# 5V_and_3V3_Outputs.net
KiCad netlist of a schematic drawn in Altium Designer
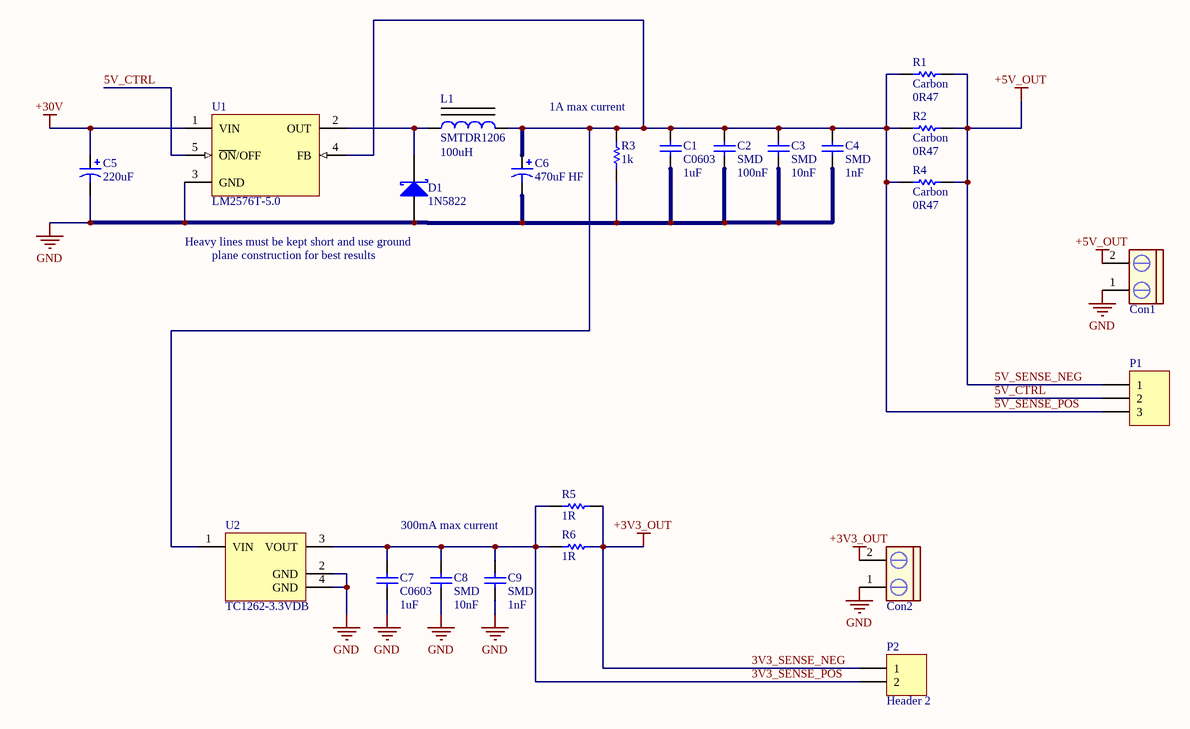
[diagram p0: 5V and 3V3 Outputs.SchDoc]

(export (version "E")
  (design (tool "Eeschema 10.0.6"))
  (components
    (comp (ref "C1")
      (value "C0603")
      (footprint "0603")
      (description "C1608X7R1C105K X7R")
      (fields (field (name "ALTIUM_VALUE") "1uF") (field (name "PUBLISHER") "Altium Limited"))
      (libsource (lib "KEMET Chip Capacitor") (part "C0603"))
    )
    (comp (ref "C2")
      (value "SMD")
      (footprint "1206")
      (description "Ceramic Chip Capacitor - Standard")
      (fields (field (name "ALTIUM_VALUE") "100nF") (field (name "PUBLISHER") "Altium Limited"))
      (libsource (lib "KEMET Chip Capacitor") (part "C1206"))
    )
    (comp (ref "C3")
      (value "SMD")
      (footprint "1206")
      (description "Ceramic Chip Capacitor - Standard")
      (fields (field (name "ALTIUM_VALUE") "10nF") (field (name "PUBLISHER") "Altium Limited"))
      (libsource (lib "KEMET Chip Capacitor") (part "C1206"))
    )
    (comp (ref "C4")
      (value "SMD")
      (footprint "1206")
      (description "Ceramic Chip Capacitor - Standard")
      (fields (field (name "ALTIUM_VALUE") "1nF") (field (name "PUBLISHER") "Altium Limited"))
      (libsource (lib "KEMET Chip Capacitor") (part "C1206"))
    )
    (comp (ref "C5")
      (value "220uF")
      (footprint "CAPPR5-10X16")
      (description "Aluminum Electrolytic Capacitor, Radial Style with Long Leads: 220uF, 63V")
      (fields (field (name "PUBLISHER") "Altium Limited"))
      (libsource (lib "Vishay Roederstein Electrolytic Radial-Lead Capacitor") (part "EKA00DD322J00"))
    )
    (comp (ref "C6")
      (value "470uF HF")
      (footprint "CAPPR5-10X20")
      (description "Aluminum Electrolytic Capacitor, Radial Style with Long Leads: 470uF, 25V")
      (fields (field (name "PUBLISHER") "Altium Limited"))
      (libsource (lib "Vishay Roederstein Electrolytic Radial-Lead Capacitor") (part "EKC00DE347E00"))
    )
    (comp (ref "C7")
      (value "C0603")
      (footprint "0603")
      (description "C1608X7R1C105K X7R")
      (fields (field (name "ALTIUM_VALUE") "1uF") (field (name "PUBLISHER") "Altium Limited"))
      (libsource (lib "KEMET Chip Capacitor") (part "C0603"))
    )
    (comp (ref "C8")
      (value "SMD")
      (footprint "1206")
      (description "Ceramic Chip Capacitor - Standard")
      (fields (field (name "ALTIUM_VALUE") "10nF") (field (name "PUBLISHER") "Altium Limited"))
      (libsource (lib "KEMET Chip Capacitor") (part "C1206"))
    )
    (comp (ref "C9")
      (value "SMD")
      (footprint "1206")
      (description "Ceramic Chip Capacitor - Standard")
      (fields (field (name "ALTIUM_VALUE") "1nF") (field (name "PUBLISHER") "Altium Limited"))
      (libsource (lib "KEMET Chip Capacitor") (part "C1206"))
    )
    (comp (ref "Con1")
      (value "Salida Buck")
      (footprint "My_CN2")
      (description "Connector blue screw")
      (libsource (lib "Mylib") (part "CON2 pin blue"))
    )
    (comp (ref "Con2")
      (value "Salida Buck")
      (footprint "My_CN2")
      (description "Connector blue screw")
      (libsource (lib "Mylib") (part "CON2 pin blue"))
    )
    (comp (ref "D1")
      (value "1N5822")
      (footprint "Vertical DO-201AD")
      (description "Generic Schottky Diode")
      (libsource (lib "NXT - Diodes") (part "Generic Schottky Diode"))
    )
    (comp (ref "L1")
      (value "SMTDR1206")
      (footprint "SMTDR1206 Inductor")
      (description "100UHY SMD 18.54X7.11MM 20% 3A 0.19E SMTDR1206-101M")
      (fields (field (name "ALTIUM_VALUE") "100uH"))
      (libsource (lib "NXT - Inductors") (part "100UHY SMD 18.54X7.11MM 20% 3A 0.19E SMTDR1206-101M"))
    )
    (comp (ref "P1")
      (value "Header 3")
      (footprint "My_1X03")
      (description "Header, 3-Pin")
      (fields (field (name "PUBLISHER") "Altium Limited"))
      (libsource (lib "Mylib") (part "Header 3"))
    )
    (comp (ref "P2")
      (value "Header 2")
      (footprint "HDR1X2")
      (description "Header, 2-Pin")
      (fields (field (name "PUBLISHER") "Altium Limited"))
      (libsource (lib "Miscellaneous Connectors") (part "Header 2"))
    )
    (comp (ref "R1")
      (value "Carbon")
      (footprint "AXIAL-0.3")
      (description "Resistor")
      (fields (field (name "ALTIUM_VALUE") "0R47") (field (name "PUBLISHER") "Altium Limited"))
      (libsource (lib "Miscellaneous Devices") (part "Res1"))
    )
    (comp (ref "R2")
      (value "Carbon")
      (footprint "AXIAL-0.3")
      (description "Resistor")
      (fields (field (name "ALTIUM_VALUE") "0R47") (field (name "PUBLISHER") "Altium Limited"))
      (libsource (lib "Miscellaneous Devices") (part "Res1"))
    )
    (comp (ref "R3")
      (value "1k")
      (footprint "8RB-1206")
      (fields (field (name "Comment") "SMD") (field (name "PUBLISHER") "Altium Limited"))
      (libsource (lib "Panasonic Resistor") (part "ERJ8BQ"))
    )
    (comp (ref "R4")
      (value "Carbon")
      (footprint "AXIAL-0.3")
      (description "Resistor")
      (fields (field (name "ALTIUM_VALUE") "0R47") (field (name "PUBLISHER") "Altium Limited"))
      (libsource (lib "Miscellaneous Devices") (part "Res1"))
    )
    (comp (ref "R5")
      (value "1R")
      (footprint "8RB-1206")
      (fields (field (name "Comment") "SMD") (field (name "PUBLISHER") "Altium Limited"))
      (libsource (lib "Panasonic Resistor") (part "ERJ8BQ"))
    )
    (comp (ref "R6")
      (value "1R")
      (footprint "8RB-1206")
      (fields (field (name "Comment") "SMD") (field (name "PUBLISHER") "Altium Limited"))
      (libsource (lib "Panasonic Resistor") (part "ERJ8BQ"))
    )
    (comp (ref "U1")
      (value "LM2576T-5.0")
      (footprint "T05A")
      (description "SIMPLE SWITCHER® 3A Step-Down Voltage Regulator, 5-pin TO-220")
      (fields
        (field (name "MANUFACTURER") "National Semiconductor")
        (field (name "PUBLISHER") "Altium Limited")
      )
      (libsource (lib "NSC Switcher") (part "LM2576T-5.0"))
    )
    (comp (ref "U2")
      (value "TC1262-3.3VDB")
      (footprint "SOT-223-DB3_N")
      (description "500mA Fixed Output CMOS LDO, 3-Pin SOT-223, Extended Temperature")
      (fields (field (name "PUBLISHER") "Altium Limited"))
      (libsource (lib "Microchip Power Mgt Line Regulator") (part "TC1262-3.3VDB"))
    )
  )
  (nets
    (net (code "1") (name "+3V3_OUT") (class "Default")
      (node (ref "Con2") (pin "2") (pinfunction "2_2") (pintype "passive"))
      (node (ref "P2") (pin "1") (pinfunction "1_1") (pintype "passive"))
      (node (ref "R5") (pin "2") (pinfunction "2_2") (pintype "passive"))
      (node (ref "R6") (pin "2") (pinfunction "2_2") (pintype "passive"))
    )
    (net (code "2") (name "+5V_OUT") (class "Default")
      (node (ref "Con1") (pin "2") (pinfunction "2_2") (pintype "passive"))
      (node (ref "P1") (pin "1") (pinfunction "1_1") (pintype "passive"))
      (node (ref "R1") (pin "2") (pinfunction "2_2") (pintype "passive"))
      (node (ref "R2") (pin "2") (pinfunction "2_2") (pintype "passive"))
      (node (ref "R4") (pin "2") (pinfunction "2_2") (pintype "passive"))
    )
    (net (code "3") (name "+30V") (class "Default")
      (node (ref "C5") (pin "1") (pinfunction "1_1") (pintype "passive"))
      (node (ref "U1") (pin "1") (pinfunction "VIN_1") (pintype "power_in"))
    )
    (net (code "4") (name "/3V3_SENSE_POS") (class "Default")
      (node (ref "C7") (pin "2") (pinfunction "2_2") (pintype "passive"))
      (node (ref "C8") (pin "2") (pinfunction "2_2") (pintype "passive"))
      (node (ref "C9") (pin "2") (pinfunction "2_2") (pintype "passive"))
      (node (ref "P2") (pin "2") (pinfunction "2_2") (pintype "passive"))
      (node (ref "R5") (pin "1") (pinfunction "1_1") (pintype "passive"))
      (node (ref "R6") (pin "1") (pinfunction "1_1") (pintype "passive"))
      (node (ref "U2") (pin "3") (pinfunction "VOUT_3") (pintype "power_in"))
    )
    (net (code "5") (name "/5V_CTRL") (class "Default")
      (node (ref "P1") (pin "2") (pinfunction "2_2") (pintype "passive"))
      (node (ref "U1") (pin "5") (pinfunction "~{ON}/OFF_5") (pintype "input"))
    )
    (net (code "6") (name "/5V_SENSE_POS") (class "Default")
      (node (ref "C1") (pin "2") (pinfunction "2_2") (pintype "passive"))
      (node (ref "C2") (pin "2") (pinfunction "2_2") (pintype "passive"))
      (node (ref "C3") (pin "2") (pinfunction "2_2") (pintype "passive"))
      (node (ref "C4") (pin "2") (pinfunction "2_2") (pintype "passive"))
      (node (ref "C6") (pin "1") (pinfunction "1_1") (pintype "passive"))
      (node (ref "L1") (pin "2") (pinfunction "2_2") (pintype "passive"))
      (node (ref "P1") (pin "3") (pinfunction "3_3") (pintype "passive"))
      (node (ref "R1") (pin "1") (pinfunction "1_1") (pintype "passive"))
      (node (ref "R2") (pin "1") (pinfunction "1_1") (pintype "passive"))
      (node (ref "R3") (pin "2") (pinfunction "2_2") (pintype "passive"))
      (node (ref "R4") (pin "1") (pinfunction "1_1") (pintype "passive"))
      (node (ref "U1") (pin "4") (pinfunction "FB_4") (pintype "input"))
      (node (ref "U2") (pin "1") (pinfunction "VIN_1") (pintype "power_in"))
    )
    (net (code "7") (name "GND") (class "Default")
      (node (ref "C1") (pin "1") (pinfunction "1_1") (pintype "passive"))
      (node (ref "C2") (pin "1") (pinfunction "1_1") (pintype "passive"))
      (node (ref "C3") (pin "1") (pinfunction "1_1") (pintype "passive"))
      (node (ref "C4") (pin "1") (pinfunction "1_1") (pintype "passive"))
      (node (ref "C5") (pin "2") (pinfunction "2_2") (pintype "passive"))
      (node (ref "C6") (pin "2") (pinfunction "2_2") (pintype "passive"))
      (node (ref "C7") (pin "1") (pinfunction "1_1") (pintype "passive"))
      (node (ref "C8") (pin "1") (pinfunction "1_1") (pintype "passive"))
      (node (ref "C9") (pin "1") (pinfunction "1_1") (pintype "passive"))
      (node (ref "Con1") (pin "1") (pinfunction "1_1") (pintype "passive"))
      (node (ref "Con2") (pin "1") (pinfunction "1_1") (pintype "passive"))
      (node (ref "D1") (pin "1") (pinfunction "A_1") (pintype "passive"))
      (node (ref "R3") (pin "1") (pinfunction "1_1") (pintype "passive"))
      (node (ref "U1") (pin "3") (pinfunction "GND_3") (pintype "power_in"))
      (node (ref "U2") (pin "2") (pinfunction "GND_2") (pintype "power_in"))
      (node (ref "U2") (pin "4") (pinfunction "GND_4") (pintype "power_in"))
    )
    (net (code "8") (name "Net-(D1-K)") (class "Default")
      (node (ref "D1") (pin "2") (pinfunction "K_2") (pintype "passive"))
      (node (ref "L1") (pin "1") (pinfunction "1_1") (pintype "passive"))
      (node (ref "U1") (pin "2") (pinfunction "OUT_2") (pintype "power_in"))
    )
  )
)
